# 20_to__12.net
KiCad netlist of a schematic drawn in Altium Designer
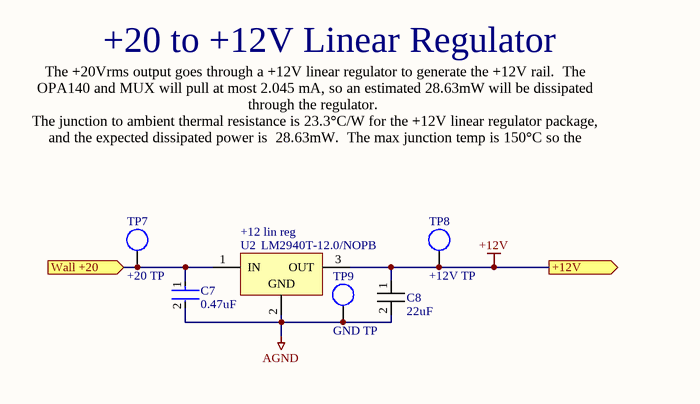
[diagram p0: +20_to_+12.SchDoc]

(export (version "E")
  (design (tool "Eeschema 10.0.6"))
  (components
    (comp (ref "C7")
      (value "0.47uF")
      (footprint "FP-C0805C-DG-MFG")
      (description "CAP CER 10UF 10V X5R 0805")
      (fields (field (name "TOLERANCE") "10%") (field (name "MANUFACTURER PART NUMBER") "C0805C106K8PACTU"))
      (libsource (lib "Altium Content Vault") (part "11868f565c42a9108669ba33697ecf6"))
    )
    (comp (ref "C8")
      (value "22uF")
      (footprint "CAPPRD200W50D550H1250")
      (libsource (lib "California Institute of Technology") (part "New symbol 1"))
    )
    (comp (ref "TP7")
      (value "+20 TP")
      (footprint "PCBComponent_1")
      (libsource (lib "test-point") (part "Component_1"))
    )
    (comp (ref "TP8")
      (value "+12V TP")
      (footprint "PCBComponent_1")
      (libsource (lib "test-point") (part "Component_1"))
    )
    (comp (ref "TP9")
      (value "GND TP")
      (footprint "PCBComponent_1")
      (libsource (lib "test-point") (part "Component_1"))
    )
    (comp (ref "U2")
      (value "LM2940T-12.0/NOPB")
      (footprint "NDE0003A")
      (description "1A Low Dropout Regulator, 3-pin TO-220, Pb-Free")
      (fields (field (name "MANUFACTURER") "Texas Instruments"))
      (libsource (lib "Altium Content Vault") (part "PM-REG-LM2940-SIL3"))
    )
  )
  (nets
    (net (code "1") (name "+12V") (class "Default")
      (node (ref "C8") (pin "1") (pinfunction "+_1") (pintype "passive"))
      (node (ref "TP8") (pin "TP") (pinfunction "TP_TP") (pintype "passive"))
      (node (ref "U2") (pin "3") (pinfunction "OUT_3") (pintype "power_in"))
    )
    (net (code "2") (name "/Wall +20") (class "Default")
      (node (ref "C7") (pin "1") (pinfunction "1_1") (pintype "passive"))
      (node (ref "TP7") (pin "TP") (pinfunction "TP_TP") (pintype "passive"))
      (node (ref "U2") (pin "1") (pinfunction "IN_1") (pintype "power_in"))
    )
    (net (code "3") (name "AGND") (class "Default")
      (node (ref "C7") (pin "2") (pinfunction "2_2") (pintype "passive"))
      (node (ref "C8") (pin "2") (pinfunction "-_2") (pintype "passive"))
      (node (ref "TP9") (pin "TP") (pinfunction "TP_TP") (pintype "passive"))
      (node (ref "U2") (pin "2") (pinfunction "GND_2") (pintype "power_in"))
    )
  )
)
